# indicator.net
KiCad netlist of a schematic drawn in Altium Designer
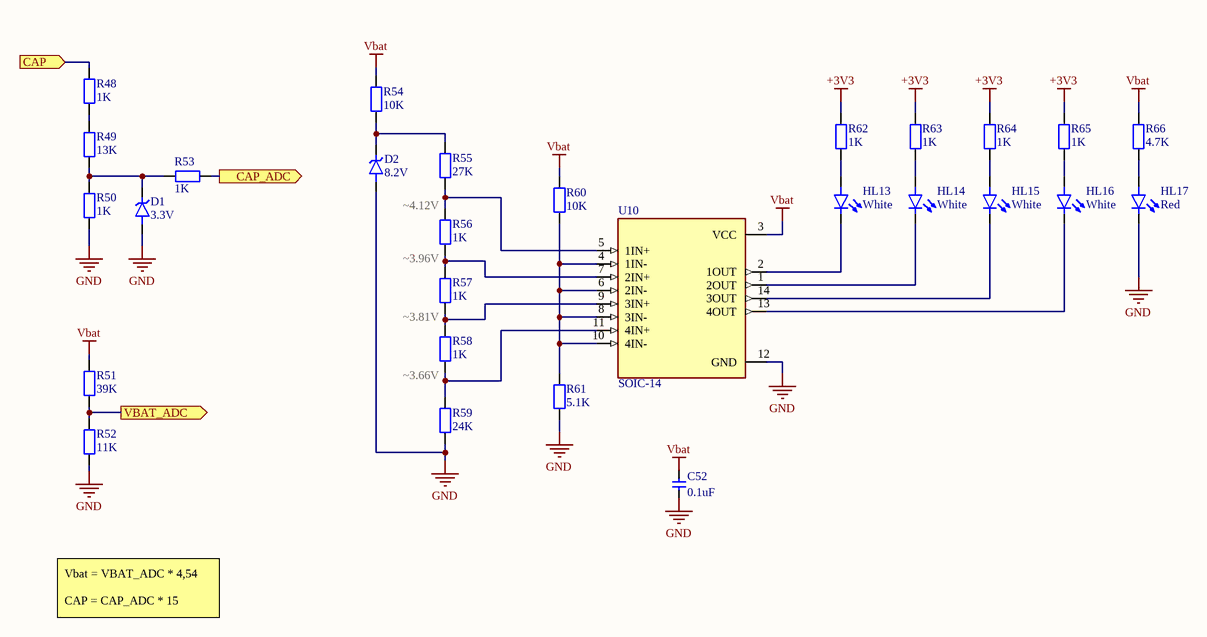
[diagram p0: indicator.SchDoc]

(export (version "E")
  (design (tool "Eeschema 10.0.6"))
  (components
    (comp (ref "C52")
      (value "0.1uF")
      (footprint "CAP0805")
      (description "Ceramic SMD Cap")
      (libsource (lib "Asterisk") (part "CAP Ceramic"))
    )
    (comp (ref "D1")
      (value "3.3V")
      (footprint "SOD-80")
      (description "Zener Diode\r\nBZV55C8V2")
      (libsource (lib "Asterisk") (part "Diode Zener"))
    )
    (comp (ref "D2")
      (value "8.2V")
      (footprint "SOD-80")
      (description "Zener Diode\r\nBZV55C8V2")
      (libsource (lib "Asterisk") (part "Diode Zener"))
    )
    (comp (ref "HL13")
      (value "White")
      (footprint "LED0603_GREEN")
      (description "LED smd")
      (libsource (lib "Asterisk") (part "LED"))
    )
    (comp (ref "HL14")
      (value "White")
      (footprint "LED0603_GREEN")
      (description "LED smd")
      (libsource (lib "Asterisk") (part "LED"))
    )
    (comp (ref "HL15")
      (value "White")
      (footprint "LED0603_GREEN")
      (description "LED smd")
      (libsource (lib "Asterisk") (part "LED"))
    )
    (comp (ref "HL16")
      (value "White")
      (footprint "LED0603_GREEN")
      (description "LED smd")
      (libsource (lib "Asterisk") (part "LED"))
    )
    (comp (ref "HL17")
      (value "Red")
      (footprint "LED0603_RED")
      (description "LED smd")
      (libsource (lib "Asterisk") (part "LED"))
    )
    (comp (ref "R48")
      (value "1K")
      (footprint "RES0805")
      (description "RES smd")
      (libsource (lib "Asterisk") (part "RES"))
    )
    (comp (ref "R49")
      (value "13K")
      (footprint "RES0805")
      (description "RES smd")
      (libsource (lib "Asterisk") (part "RES"))
    )
    (comp (ref "R50")
      (value "1K")
      (footprint "RES0805")
      (description "RES smd")
      (libsource (lib "Asterisk") (part "RES"))
    )
    (comp (ref "R51")
      (value "39K")
      (footprint "RES0805")
      (description "RES smd")
      (libsource (lib "Asterisk") (part "RES"))
    )
    (comp (ref "R52")
      (value "11K")
      (footprint "RES0805")
      (description "RES smd")
      (libsource (lib "Asterisk") (part "RES"))
    )
    (comp (ref "R53")
      (value "1K")
      (footprint "RES0805")
      (description "RES smd")
      (libsource (lib "Asterisk") (part "RES"))
    )
    (comp (ref "R54")
      (value "10K")
      (footprint "RES0805")
      (description "RES smd")
      (libsource (lib "Asterisk") (part "RES"))
    )
    (comp (ref "R55")
      (value "27K")
      (footprint "RES0805")
      (description "RES smd")
      (libsource (lib "Asterisk") (part "RES"))
    )
    (comp (ref "R56")
      (value "1K")
      (footprint "RES0805")
      (description "RES smd")
      (libsource (lib "Asterisk") (part "RES"))
    )
    (comp (ref "R57")
      (value "1K")
      (footprint "RES0805")
      (description "RES smd")
      (libsource (lib "Asterisk") (part "RES"))
    )
    (comp (ref "R58")
      (value "1K")
      (footprint "RES0805")
      (description "RES smd")
      (libsource (lib "Asterisk") (part "RES"))
    )
    (comp (ref "R59")
      (value "24K")
      (footprint "RES0805")
      (description "RES smd")
      (libsource (lib "Asterisk") (part "RES"))
    )
    (comp (ref "R60")
      (value "10K")
      (footprint "RES0805")
      (description "RES smd")
      (libsource (lib "Asterisk") (part "RES"))
    )
    (comp (ref "R61")
      (value "5.1K")
      (footprint "RES0805")
      (description "RES smd")
      (libsource (lib "Asterisk") (part "RES"))
    )
    (comp (ref "R62")
      (value "1K")
      (footprint "RES0805")
      (description "RES smd")
      (libsource (lib "Asterisk") (part "RES"))
    )
    (comp (ref "R63")
      (value "1K")
      (footprint "RES0805")
      (description "RES smd")
      (libsource (lib "Asterisk") (part "RES"))
    )
    (comp (ref "R64")
      (value "1K")
      (footprint "RES0805")
      (description "RES smd")
      (libsource (lib "Asterisk") (part "RES"))
    )
    (comp (ref "R65")
      (value "1K")
      (footprint "RES0805")
      (description "RES smd")
      (libsource (lib "Asterisk") (part "RES"))
    )
    (comp (ref "R66")
      (value "4.7K")
      (footprint "RES0805")
      (description "RES smd")
      (libsource (lib "Asterisk") (part "RES"))
    )
    (comp (ref "U10")
      (value "SOIC-14")
      (footprint "SOIC-14")
      (description "Quad differential comparator")
      (libsource (lib "Asterisk") (part "LM139DR"))
    )
  )
  (nets
    (net (code "1") (name "+3V3") (class "Default")
      (node (ref "R62") (pin "2") (pinfunction "2_2") (pintype "passive"))
      (node (ref "R63") (pin "2") (pinfunction "2_2") (pintype "passive"))
      (node (ref "R64") (pin "2") (pinfunction "2_2") (pintype "passive"))
      (node (ref "R65") (pin "2") (pinfunction "2_2") (pintype "passive"))
    )
    (net (code "2") (name "/CAP") (class "Default")
      (node (ref "R48") (pin "2") (pinfunction "2_2") (pintype "passive"))
    )
    (net (code "3") (name "/CAP_ADC") (class "Default")
      (node (ref "R53") (pin "1") (pinfunction "1_1") (pintype "passive"))
    )
    (net (code "4") (name "/VBAT_ADC") (class "Default")
      (node (ref "R51") (pin "1") (pinfunction "1_1") (pintype "passive"))
      (node (ref "R52") (pin "2") (pinfunction "2_2") (pintype "passive"))
    )
    (net (code "5") (name "GND") (class "Default")
      (node (ref "C52") (pin "1") (pinfunction "1_1") (pintype "passive"))
      (node (ref "D1") (pin "A") (pinfunction "A_A") (pintype "passive"))
      (node (ref "D2") (pin "A") (pinfunction "A_A") (pintype "passive"))
      (node (ref "HL17") (pin "1") (pinfunction "K_1") (pintype "passive"))
      (node (ref "R50") (pin "1") (pinfunction "1_1") (pintype "passive"))
      (node (ref "R52") (pin "1") (pinfunction "1_1") (pintype "passive"))
      (node (ref "R59") (pin "1") (pinfunction "1_1") (pintype "passive"))
      (node (ref "R61") (pin "1") (pinfunction "1_1") (pintype "passive"))
      (node (ref "U10") (pin "12") (pinfunction "GND_12") (pintype "power_in"))
    )
    (net (code "6") (name "Net-(D1-PadK)") (class "Default")
      (node (ref "D1") (pin "K") (pinfunction "K_K") (pintype "passive"))
      (node (ref "R49") (pin "1") (pinfunction "1_1") (pintype "passive"))
      (node (ref "R50") (pin "2") (pinfunction "2_2") (pintype "passive"))
      (node (ref "R53") (pin "2") (pinfunction "2_2") (pintype "passive"))
    )
    (net (code "7") (name "Net-(D2-PadK)") (class "Default")
      (node (ref "D2") (pin "K") (pinfunction "K_K") (pintype "passive"))
      (node (ref "R54") (pin "1") (pinfunction "1_1") (pintype "passive"))
      (node (ref "R55") (pin "2") (pinfunction "2_2") (pintype "passive"))
    )
    (net (code "8") (name "Net-(HL13-A)") (class "Default")
      (node (ref "HL13") (pin "2") (pinfunction "A_2") (pintype "passive"))
      (node (ref "R62") (pin "1") (pinfunction "1_1") (pintype "passive"))
    )
    (net (code "9") (name "Net-(HL13-K)") (class "Default")
      (node (ref "HL13") (pin "1") (pinfunction "K_1") (pintype "passive"))
      (node (ref "U10") (pin "2") (pinfunction "1OUT_2") (pintype "output"))
    )
    (net (code "10") (name "Net-(HL14-A)") (class "Default")
      (node (ref "HL14") (pin "2") (pinfunction "A_2") (pintype "passive"))
      (node (ref "R63") (pin "1") (pinfunction "1_1") (pintype "passive"))
    )
    (net (code "11") (name "Net-(HL14-K)") (class "Default")
      (node (ref "HL14") (pin "1") (pinfunction "K_1") (pintype "passive"))
      (node (ref "U10") (pin "1") (pinfunction "2OUT_1") (pintype "output"))
    )
    (net (code "12") (name "Net-(HL15-A)") (class "Default")
      (node (ref "HL15") (pin "2") (pinfunction "A_2") (pintype "passive"))
      (node (ref "R64") (pin "1") (pinfunction "1_1") (pintype "passive"))
    )
    (net (code "13") (name "Net-(HL15-K)") (class "Default")
      (node (ref "HL15") (pin "1") (pinfunction "K_1") (pintype "passive"))
      (node (ref "U10") (pin "14") (pinfunction "3OUT_14") (pintype "output"))
    )
    (net (code "14") (name "Net-(HL16-A)") (class "Default")
      (node (ref "HL16") (pin "2") (pinfunction "A_2") (pintype "passive"))
      (node (ref "R65") (pin "1") (pinfunction "1_1") (pintype "passive"))
    )
    (net (code "15") (name "Net-(HL16-K)") (class "Default")
      (node (ref "HL16") (pin "1") (pinfunction "K_1") (pintype "passive"))
      (node (ref "U10") (pin "13") (pinfunction "4OUT_13") (pintype "output"))
    )
    (net (code "16") (name "Net-(HL17-A)") (class "Default")
      (node (ref "HL17") (pin "2") (pinfunction "A_2") (pintype "passive"))
      (node (ref "R66") (pin "1") (pinfunction "1_1") (pintype "passive"))
    )
    (net (code "17") (name "Net-(R48-Pad1)") (class "Default")
      (node (ref "R48") (pin "1") (pinfunction "1_1") (pintype "passive"))
      (node (ref "R49") (pin "2") (pinfunction "2_2") (pintype "passive"))
    )
    (net (code "18") (name "Net-(U10-1IN+)") (class "Default")
      (node (ref "R55") (pin "1") (pinfunction "1_1") (pintype "passive"))
      (node (ref "R56") (pin "2") (pinfunction "2_2") (pintype "passive"))
      (node (ref "U10") (pin "5") (pinfunction "1IN+_5") (pintype "input"))
    )
    (net (code "19") (name "Net-(U10-1IN-)") (class "Default")
      (node (ref "R60") (pin "1") (pinfunction "1_1") (pintype "passive"))
      (node (ref "R61") (pin "2") (pinfunction "2_2") (pintype "passive"))
      (node (ref "U10") (pin "10") (pinfunction "4IN-_10") (pintype "input"))
      (node (ref "U10") (pin "4") (pinfunction "1IN-_4") (pintype "input"))
      (node (ref "U10") (pin "6") (pinfunction "2IN-_6") (pintype "input"))
      (node (ref "U10") (pin "8") (pinfunction "3IN-_8") (pintype "input"))
    )
    (net (code "20") (name "Net-(U10-2IN+)") (class "Default")
      (node (ref "R56") (pin "1") (pinfunction "1_1") (pintype "passive"))
      (node (ref "R57") (pin "2") (pinfunction "2_2") (pintype "passive"))
      (node (ref "U10") (pin "7") (pinfunction "2IN+_7") (pintype "input"))
    )
    (net (code "21") (name "Net-(U10-3IN+)") (class "Default")
      (node (ref "R57") (pin "1") (pinfunction "1_1") (pintype "passive"))
      (node (ref "R58") (pin "2") (pinfunction "2_2") (pintype "passive"))
      (node (ref "U10") (pin "9") (pinfunction "3IN+_9") (pintype "input"))
    )
    (net (code "22") (name "Net-(U10-4IN+)") (class "Default")
      (node (ref "R58") (pin "1") (pinfunction "1_1") (pintype "passive"))
      (node (ref "R59") (pin "2") (pinfunction "2_2") (pintype "passive"))
      (node (ref "U10") (pin "11") (pinfunction "4IN+_11") (pintype "input"))
    )
    (net (code "23") (name "Vbat") (class "Default")
      (node (ref "C52") (pin "2") (pinfunction "2_2") (pintype "passive"))
      (node (ref "R51") (pin "2") (pinfunction "2_2") (pintype "passive"))
      (node (ref "R54") (pin "2") (pinfunction "2_2") (pintype "passive"))
      (node (ref "R60") (pin "2") (pinfunction "2_2") (pintype "passive"))
      (node (ref "R66") (pin "2") (pinfunction "2_2") (pintype "passive"))
      (node (ref "U10") (pin "3") (pinfunction "VCC_3") (pintype "power_in"))
    )
  )
)
